# ATMEGA328PB_EVAL_R2.net
KiCad netlist of a schematic drawn in EAGLE
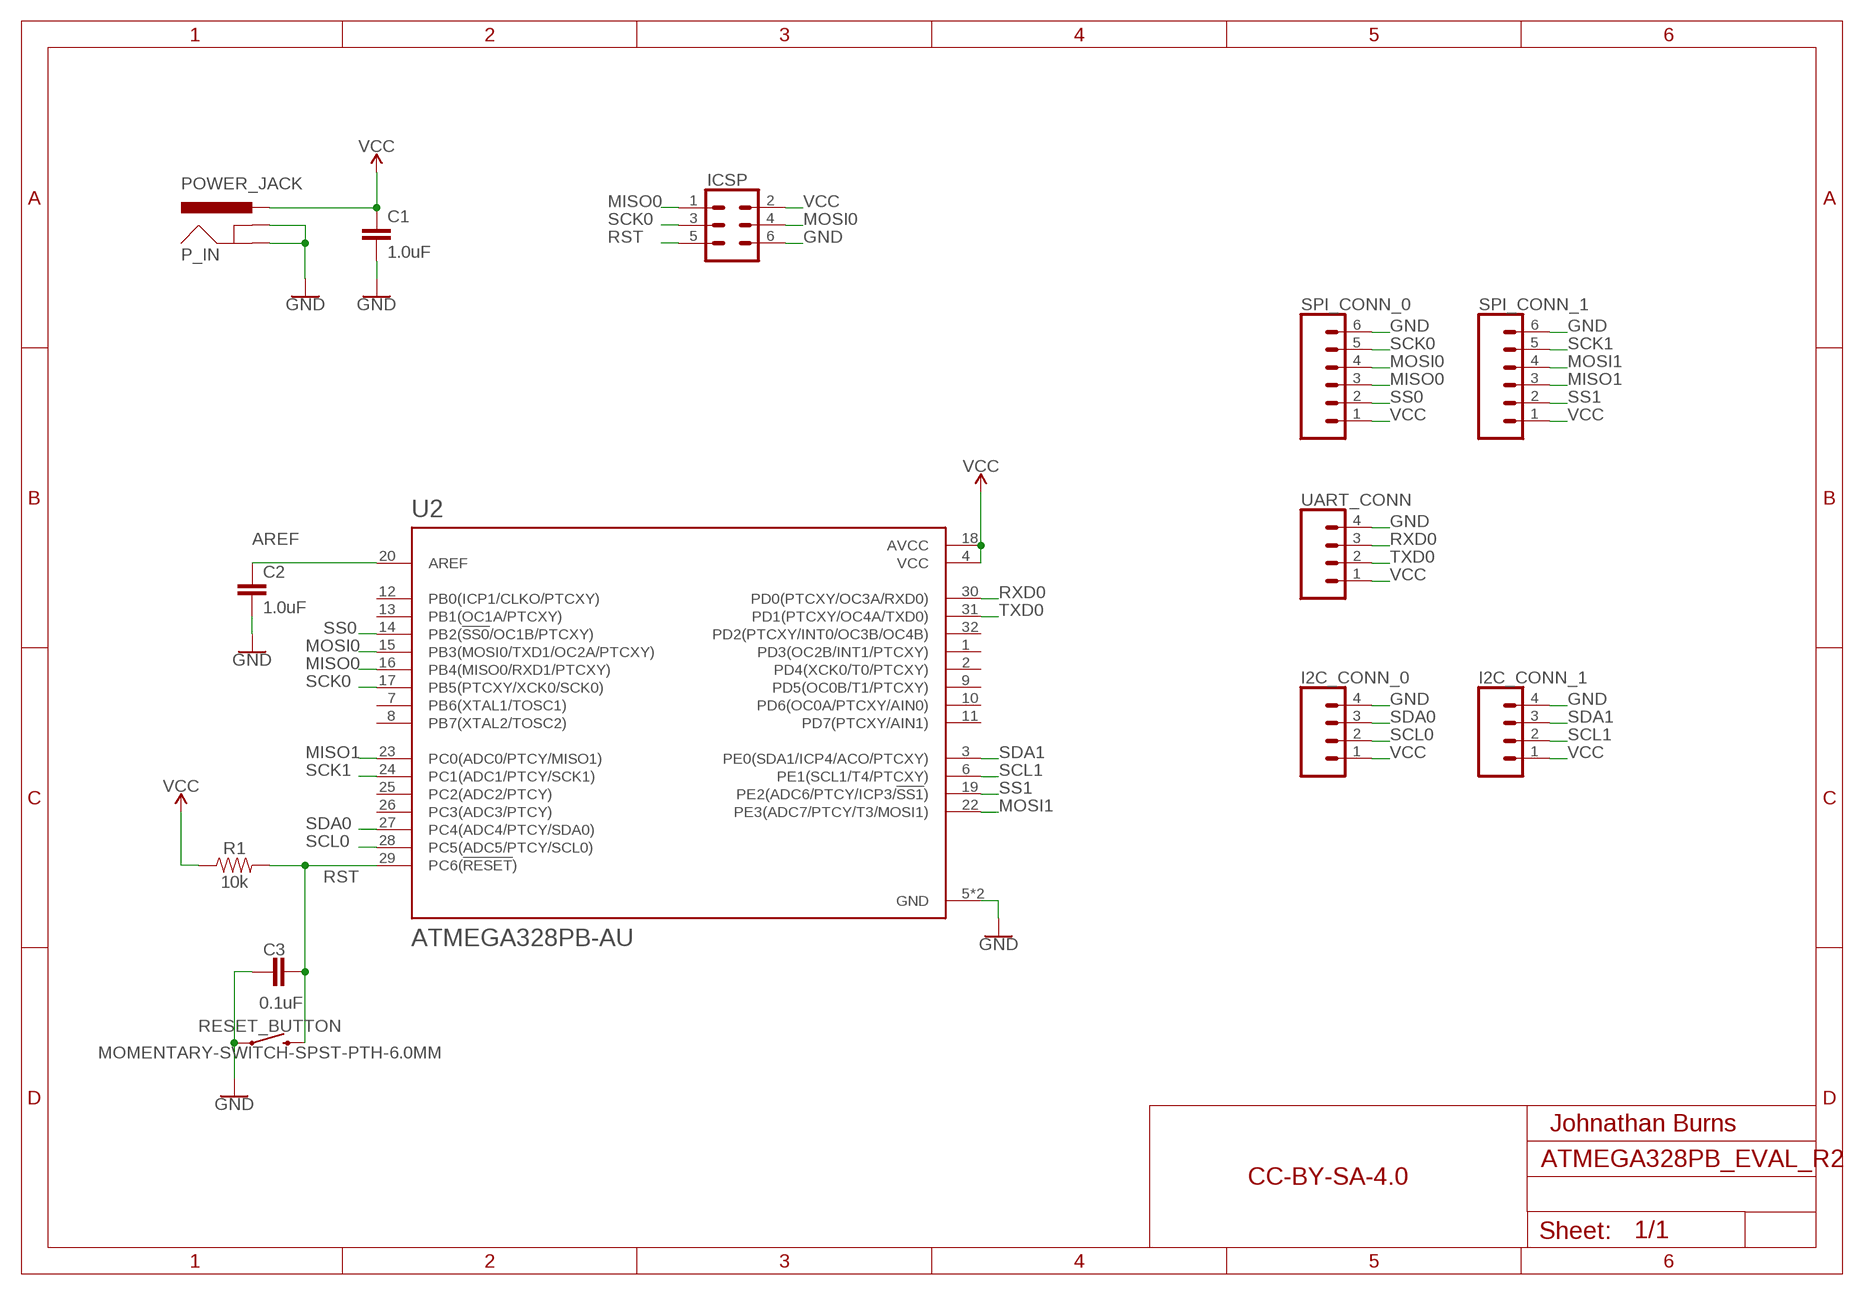
[diagram p0: schematic, sheet 1]

(export (version "E")
  (design (tool "Eeschema 10.0.6"))
  (components
    (comp (ref "C1")
      (value "1.0uF")
      (footprint "eagle-import:0603")
      (libsource (lib "eagle-import") (part "1.0UF-0603-16V-10%"))
    )
    (comp (ref "C2")
      (value "1.0uF")
      (footprint "eagle-import:0603")
      (libsource (lib "eagle-import") (part "1.0UF-0603-16V-10%"))
    )
    (comp (ref "C3")
      (value "0.1uF")
      (footprint "eagle-import:0603")
      (libsource (lib "eagle-import") (part "0.1UF-0603-25V-(+80/-20%)"))
    )
    (comp (ref "I2C_CONN_0")
      (value "CONN_04")
      (footprint "eagle-import:1X04")
      (libsource (lib "eagle-import") (part "CONN_04"))
    )
    (comp (ref "I2C_CONN_1")
      (value "CONN_04")
      (footprint "eagle-import:1X04")
      (libsource (lib "eagle-import") (part "CONN_04"))
    )
    (comp (ref "ICSP")
      (value "CONN_03X2NO_SILK")
      (footprint "eagle-import:2X3-NS")
      (libsource (lib "eagle-import") (part "CONN_03X2NO_SILK"))
    )
    (comp (ref "P_IN")
      (value "POWER_JACK")
      (footprint "eagle-import:POWER_JACK_PTH")
      (libsource (lib "eagle-import") (part "POWER_JACK"))
    )
    (comp (ref "R1")
      (value "10k")
      (footprint "eagle-import:0603")
      (libsource (lib "eagle-import") (part "10KOHM-0603-1/10W-1%"))
    )
    (comp (ref "RESET_BUTTON")
      (value "MOMENTARY-SWITCH-SPST-PTH-6.0MM")
      (footprint "eagle-import:TACTILE_SWITCH_PTH_6.0MM")
      (libsource (lib "eagle-import") (part "MOMENTARY-SWITCH-SPST-PTH-6.0MM"))
    )
    (comp (ref "SPI_CONN_0")
      (value "CONN_06SILK_FEMALE_PTH")
      (footprint "eagle-import:1X06")
      (libsource (lib "eagle-import") (part "CONN_06SILK_FEMALE_PTH"))
    )
    (comp (ref "SPI_CONN_1")
      (value "CONN_06SILK_FEMALE_PTH")
      (footprint "eagle-import:1X06")
      (libsource (lib "eagle-import") (part "CONN_06SILK_FEMALE_PTH"))
    )
    (comp (ref "U2")
      (value "ATMEGA328PB-AU")
      (footprint "eagle-import:QFP80P900X900X120-32N")
      (fields (field (name "MF") "Microchip Technology / Atmel"))
      (libsource (lib "eagle-import") (part "ATMEGA328PB-AU"))
    )
    (comp (ref "UART_CONN")
      (value "CONN_04")
      (footprint "eagle-import:1X04")
      (libsource (lib "eagle-import") (part "CONN_04"))
    )
  )
  (nets
    (net (code "1") (name "/AREF") (class "Default")
      (node (ref "C2") (pin "1") (pinfunction "1_1") (pintype "passive"))
      (node (ref "U2") (pin "20") (pinfunction "AREF_20") (pintype "input"))
    )
    (net (code "2") (name "/MISO0") (class "Default")
      (node (ref "ICSP") (pin "1") (pinfunction "1_1") (pintype "bidirectional"))
      (node (ref "SPI_CONN_0") (pin "3") (pinfunction "3_3") (pintype "passive"))
      (node (ref "U2") (pin "16") (pinfunction "PB4(MISO0/RXD1/PTCXY)_16") (pintype "bidirectional"))
    )
    (net (code "3") (name "/MISO1") (class "Default")
      (node (ref "SPI_CONN_1") (pin "3") (pinfunction "3_3") (pintype "passive"))
      (node (ref "U2") (pin "23") (pinfunction "PC0(ADC0/PTCY/MISO1)_23") (pintype "bidirectional"))
    )
    (net (code "4") (name "/MOSI0") (class "Default")
      (node (ref "ICSP") (pin "4") (pinfunction "4_4") (pintype "bidirectional"))
      (node (ref "SPI_CONN_0") (pin "4") (pinfunction "4_4") (pintype "passive"))
      (node (ref "U2") (pin "15") (pinfunction "PB3(MOSI0/TXD1/OC2A/PTCXY)_15") (pintype "bidirectional"))
    )
    (net (code "5") (name "/MOSI1") (class "Default")
      (node (ref "SPI_CONN_1") (pin "4") (pinfunction "4_4") (pintype "passive"))
      (node (ref "U2") (pin "22") (pinfunction "PE3(ADC7/PTCY/T3/MOSI1)_22") (pintype "bidirectional"))
    )
    (net (code "6") (name "/RST") (class "Default")
      (node (ref "C3") (pin "2") (pinfunction "2_2") (pintype "passive"))
      (node (ref "ICSP") (pin "5") (pinfunction "5_5") (pintype "bidirectional"))
      (node (ref "R1") (pin "2") (pinfunction "2_2") (pintype "passive"))
      (node (ref "RESET_BUTTON") (pin "3") (pinfunction "2_3") (pintype "passive"))
      (node (ref "U2") (pin "29") (pinfunction "PC6(~{RESET})_29") (pintype "bidirectional"))
    )
    (net (code "7") (name "/RXD0") (class "Default")
      (node (ref "U2") (pin "30") (pinfunction "PD0(PTCXY/OC3A/RXD0)_30") (pintype "bidirectional"))
      (node (ref "UART_CONN") (pin "3") (pinfunction "3_3") (pintype "passive"))
    )
    (net (code "8") (name "/SCK0") (class "Default")
      (node (ref "ICSP") (pin "3") (pinfunction "3_3") (pintype "bidirectional"))
      (node (ref "SPI_CONN_0") (pin "5") (pinfunction "5_5") (pintype "passive"))
      (node (ref "U2") (pin "17") (pinfunction "PB5(PTCXY/XCK0/SCK0)_17") (pintype "bidirectional"))
    )
    (net (code "9") (name "/SCK1") (class "Default")
      (node (ref "SPI_CONN_1") (pin "5") (pinfunction "5_5") (pintype "passive"))
      (node (ref "U2") (pin "24") (pinfunction "PC1(ADC1/PTCY/SCK1)_24") (pintype "bidirectional"))
    )
    (net (code "10") (name "/SCL0") (class "Default")
      (node (ref "I2C_CONN_0") (pin "2") (pinfunction "2_2") (pintype "passive"))
      (node (ref "U2") (pin "28") (pinfunction "PC5(ADC5/PTCY/SCL0)_28") (pintype "bidirectional"))
    )
    (net (code "11") (name "/SCL1") (class "Default")
      (node (ref "I2C_CONN_1") (pin "2") (pinfunction "2_2") (pintype "passive"))
      (node (ref "U2") (pin "6") (pinfunction "PE1(SCL1/T4/PTCXY)_6") (pintype "bidirectional"))
    )
    (net (code "12") (name "/SDA0") (class "Default")
      (node (ref "I2C_CONN_0") (pin "3") (pinfunction "3_3") (pintype "passive"))
      (node (ref "U2") (pin "27") (pinfunction "PC4(ADC4/PTCY/SDA0)_27") (pintype "bidirectional"))
    )
    (net (code "13") (name "/SDA1") (class "Default")
      (node (ref "I2C_CONN_1") (pin "3") (pinfunction "3_3") (pintype "passive"))
      (node (ref "U2") (pin "3") (pinfunction "PE0(SDA1/ICP4/ACO/PTCXY)_3") (pintype "bidirectional"))
    )
    (net (code "14") (name "/SS0") (class "Default")
      (node (ref "SPI_CONN_0") (pin "2") (pinfunction "2_2") (pintype "passive"))
      (node (ref "U2") (pin "14") (pinfunction "PB2(~{SS0}/OC1B/PTCXY)_14") (pintype "bidirectional"))
    )
    (net (code "15") (name "/SS1") (class "Default")
      (node (ref "SPI_CONN_1") (pin "2") (pinfunction "2_2") (pintype "passive"))
      (node (ref "U2") (pin "19") (pinfunction "PE2(ADC6/PTCY/ICP3/~{SS1})_19") (pintype "bidirectional"))
    )
    (net (code "16") (name "/TXD0") (class "Default")
      (node (ref "U2") (pin "31") (pinfunction "PD1(PTCXY/OC4A/TXD0)_31") (pintype "bidirectional"))
      (node (ref "UART_CONN") (pin "2") (pinfunction "2_2") (pintype "passive"))
    )
    (net (code "17") (name "GND") (class "Default")
      (node (ref "C1") (pin "2") (pinfunction "2_2") (pintype "passive"))
      (node (ref "C2") (pin "2") (pinfunction "2_2") (pintype "passive"))
      (node (ref "C3") (pin "1") (pinfunction "1_1") (pintype "passive"))
      (node (ref "I2C_CONN_0") (pin "4") (pinfunction "4_4") (pintype "passive"))
      (node (ref "I2C_CONN_1") (pin "4") (pinfunction "4_4") (pintype "passive"))
      (node (ref "ICSP") (pin "6") (pinfunction "6_6") (pintype "bidirectional"))
      (node (ref "P_IN") (pin "GND") (pinfunction "GND_GND") (pintype "bidirectional"))
      (node (ref "P_IN") (pin "GNDBREAK") (pinfunction "GNDBREAK_GNDBREAK") (pintype "bidirectional"))
      (node (ref "RESET_BUTTON") (pin "1") (pinfunction "1_1") (pintype "passive"))
      (node (ref "SPI_CONN_0") (pin "6") (pinfunction "6_6") (pintype "passive"))
      (node (ref "SPI_CONN_1") (pin "6") (pinfunction "6_6") (pintype "passive"))
      (node (ref "U2") (pin "21") (pinfunction "GND_21") (pintype "power_in"))
      (node (ref "U2") (pin "5") (pinfunction "GND_5") (pintype "power_in"))
      (node (ref "UART_CONN") (pin "4") (pinfunction "4_4") (pintype "passive"))
    )
    (net (code "18") (name "VCC") (class "Default")
      (node (ref "C1") (pin "1") (pinfunction "1_1") (pintype "passive"))
      (node (ref "I2C_CONN_0") (pin "1") (pinfunction "1_1") (pintype "passive"))
      (node (ref "I2C_CONN_1") (pin "1") (pinfunction "1_1") (pintype "passive"))
      (node (ref "ICSP") (pin "2") (pinfunction "2_2") (pintype "bidirectional"))
      (node (ref "P_IN") (pin "PWR") (pinfunction "PWR_PWR") (pintype "bidirectional"))
      (node (ref "R1") (pin "1") (pinfunction "1_1") (pintype "passive"))
      (node (ref "SPI_CONN_0") (pin "1") (pinfunction "1_1") (pintype "passive"))
      (node (ref "SPI_CONN_1") (pin "1") (pinfunction "1_1") (pintype "passive"))
      (node (ref "U2") (pin "18") (pinfunction "AVCC_18") (pintype "power_in"))
      (node (ref "U2") (pin "4") (pinfunction "VCC_4") (pintype "power_in"))
      (node (ref "UART_CONN") (pin "1") (pinfunction "1_1") (pintype "passive"))
    )
    (net (code "19") (name "unconnected-(U2-PB0(ICP1{slash}CLKO{slash}PTCXY)-Pad12)") (class "Default")
      (node (ref "U2") (pin "12") (pinfunction "PB0(ICP1/CLKO/PTCXY)_12") (pintype "bidirectional"))
    )
    (net (code "20") (name "unconnected-(U2-PB1(OC1A{slash}PTCXY)-Pad13)") (class "Default")
      (node (ref "U2") (pin "13") (pinfunction "PB1(OC1A/PTCXY)_13") (pintype "bidirectional"))
    )
    (net (code "21") (name "unconnected-(U2-PB6(XTAL1{slash}TOSC1)-Pad7)") (class "Default")
      (node (ref "U2") (pin "7") (pinfunction "PB6(XTAL1/TOSC1)_7") (pintype "bidirectional"))
    )
    (net (code "22") (name "unconnected-(U2-PB7(XTAL2{slash}TOSC2)-Pad8)") (class "Default")
      (node (ref "U2") (pin "8") (pinfunction "PB7(XTAL2/TOSC2)_8") (pintype "bidirectional"))
    )
    (net (code "23") (name "unconnected-(U2-PC2(ADC2{slash}PTCY)-Pad25)") (class "Default")
      (node (ref "U2") (pin "25") (pinfunction "PC2(ADC2/PTCY)_25") (pintype "bidirectional"))
    )
    (net (code "24") (name "unconnected-(U2-PC3(ADC3{slash}PTCY)-Pad26)") (class "Default")
      (node (ref "U2") (pin "26") (pinfunction "PC3(ADC3/PTCY)_26") (pintype "bidirectional"))
    )
    (net (code "25") (name "unconnected-(U2-PD2(PTCXY{slash}INT0{slash}OC3B{slash}OC4B)-Pad32)") (class "Default")
      (node (ref "U2") (pin "32") (pinfunction "PD2(PTCXY/INT0/OC3B/OC4B)_32") (pintype "bidirectional"))
    )
    (net (code "26") (name "unconnected-(U2-PD3(OC2B{slash}INT1{slash}PTCXY)-Pad1)") (class "Default")
      (node (ref "U2") (pin "1") (pinfunction "PD3(OC2B/INT1/PTCXY)_1") (pintype "bidirectional"))
    )
    (net (code "27") (name "unconnected-(U2-PD4(XCK0{slash}T0{slash}PTCXY)-Pad2)") (class "Default")
      (node (ref "U2") (pin "2") (pinfunction "PD4(XCK0/T0/PTCXY)_2") (pintype "bidirectional"))
    )
    (net (code "28") (name "unconnected-(U2-PD5(OC0B{slash}T1{slash}PTCXY)-Pad9)") (class "Default")
      (node (ref "U2") (pin "9") (pinfunction "PD5(OC0B/T1/PTCXY)_9") (pintype "bidirectional"))
    )
    (net (code "29") (name "unconnected-(U2-PD6(OC0A{slash}PTCXY{slash}AIN0)-Pad10)") (class "Default")
      (node (ref "U2") (pin "10") (pinfunction "PD6(OC0A/PTCXY/AIN0)_10") (pintype "bidirectional"))
    )
    (net (code "30") (name "unconnected-(U2-PD7(PTCXY{slash}AIN1)-Pad11)") (class "Default")
      (node (ref "U2") (pin "11") (pinfunction "PD7(PTCXY/AIN1)_11") (pintype "bidirectional"))
    )
  )
)
